# Bpod_RasPi_Shim_r1.net
KiCad netlist of a schematic drawn in EAGLE
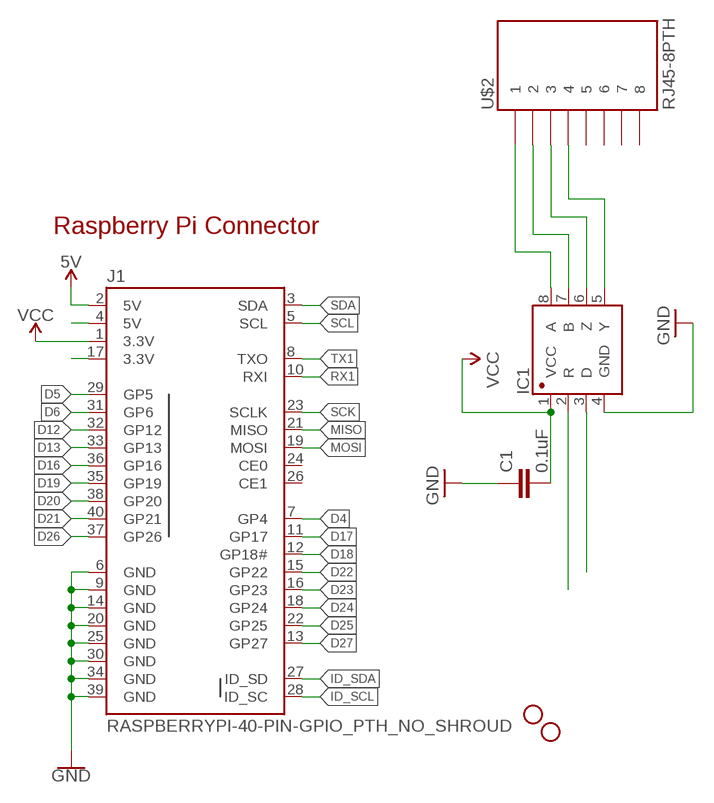
[diagram p0: schematic, sheet 1]

(export (version "E")
  (design (tool "Eeschema 10.0.6"))
  (components
    (comp (ref "C1")
      (value "0.1uF")
      (footprint "eagle-import:0805")
      (libsource (lib "eagle-import") (part "1.0UF-0805-25V-(+80/-20%)"))
    )
    (comp (ref "H3")
      (value "STAND-OFFTIGHT")
      (footprint "eagle-import:STAND-OFF-TIGHT")
      (libsource (lib "eagle-import") (part "STAND-OFFTIGHT"))
    )
    (comp (ref "H4")
      (value "STAND-OFFTIGHT")
      (footprint "eagle-import:STAND-OFF-TIGHT")
      (libsource (lib "eagle-import") (part "STAND-OFFTIGHT"))
    )
    (comp (ref "IC1")
      (value "SN65HVD31DR")
      (footprint "eagle-import:SO08")
      (libsource (lib "eagle-import") (part "SN65HVD31DR"))
    )
    (comp (ref "J1")
      (value "RASPBERRYPI-40-PIN-GPIO_PTH_NO_SHROUD")
      (footprint "eagle-import:2X20")
      (libsource (lib "eagle-import") (part "RASPBERRYPI-40-PIN-GPIO_PTH_NO_SHROUD"))
    )
    (comp (ref "U$2")
      (value "RJ45-8PTH")
      (footprint "eagle-import:RJ45-8")
      (libsource (lib "eagle-import") (part "RJ45-8PTH"))
    )
  )
  (nets
    (net (code "1") (name "5V") (class "Default")
      (node (ref "J1") (pin "2") (pinfunction "5V_2") (pintype "power_in"))
    )
    (net (code "2") (name "D4") (class "Default")
      (node (ref "J1") (pin "7") (pinfunction "GP4_7") (pintype "bidirectional"))
    )
    (net (code "3") (name "D5") (class "Default")
      (node (ref "J1") (pin "29") (pinfunction "GP5_29") (pintype "bidirectional"))
    )
    (net (code "4") (name "D6") (class "Default")
      (node (ref "J1") (pin "31") (pinfunction "GP6_31") (pintype "bidirectional"))
    )
    (net (code "5") (name "D12") (class "Default")
      (node (ref "J1") (pin "32") (pinfunction "GP12_32") (pintype "bidirectional"))
    )
    (net (code "6") (name "D13") (class "Default")
      (node (ref "J1") (pin "33") (pinfunction "GP13_33") (pintype "bidirectional"))
    )
    (net (code "7") (name "D16") (class "Default")
      (node (ref "J1") (pin "36") (pinfunction "GP16_36") (pintype "bidirectional"))
    )
    (net (code "8") (name "D17") (class "Default")
      (node (ref "J1") (pin "11") (pinfunction "GP17_11") (pintype "bidirectional"))
    )
    (net (code "9") (name "D18") (class "Default")
      (node (ref "J1") (pin "12") (pinfunction "GP18#_12") (pintype "bidirectional"))
    )
    (net (code "10") (name "D19") (class "Default")
      (node (ref "J1") (pin "35") (pinfunction "GP19_35") (pintype "bidirectional"))
    )
    (net (code "11") (name "D20") (class "Default")
      (node (ref "J1") (pin "38") (pinfunction "GP20_38") (pintype "bidirectional"))
    )
    (net (code "12") (name "D21") (class "Default")
      (node (ref "J1") (pin "40") (pinfunction "GP21_40") (pintype "bidirectional"))
    )
    (net (code "13") (name "D22") (class "Default")
      (node (ref "J1") (pin "15") (pinfunction "GP22_15") (pintype "bidirectional"))
    )
    (net (code "14") (name "D23") (class "Default")
      (node (ref "J1") (pin "16") (pinfunction "GP23_16") (pintype "bidirectional"))
    )
    (net (code "15") (name "D24") (class "Default")
      (node (ref "J1") (pin "18") (pinfunction "GP24_18") (pintype "bidirectional"))
    )
    (net (code "16") (name "D25") (class "Default")
      (node (ref "J1") (pin "22") (pinfunction "GP25_22") (pintype "bidirectional"))
    )
    (net (code "17") (name "D26") (class "Default")
      (node (ref "J1") (pin "37") (pinfunction "GP26_37") (pintype "bidirectional"))
    )
    (net (code "18") (name "D27") (class "Default")
      (node (ref "J1") (pin "13") (pinfunction "GP27_13") (pintype "bidirectional"))
    )
    (net (code "19") (name "GND") (class "Default")
      (node (ref "C1") (pin "1") (pinfunction "1_1") (pintype "passive"))
      (node (ref "IC1") (pin "4") (pinfunction "GND_4") (pintype "bidirectional"))
      (node (ref "J1") (pin "14") (pinfunction "GND_14") (pintype "power_in"))
      (node (ref "J1") (pin "20") (pinfunction "GND_20") (pintype "power_in"))
      (node (ref "J1") (pin "25") (pinfunction "GND_25") (pintype "power_in"))
      (node (ref "J1") (pin "30") (pinfunction "GND_30") (pintype "power_in"))
      (node (ref "J1") (pin "34") (pinfunction "GND_34") (pintype "power_in"))
      (node (ref "J1") (pin "39") (pinfunction "GND_39") (pintype "power_in"))
      (node (ref "J1") (pin "6") (pinfunction "GND_6") (pintype "power_in"))
      (node (ref "J1") (pin "9") (pinfunction "GND_9") (pintype "power_in"))
    )
    (net (code "20") (name "ID_SCL") (class "Default")
      (node (ref "J1") (pin "28") (pinfunction "ID_SC_28") (pintype "bidirectional"))
    )
    (net (code "21") (name "ID_SDA") (class "Default")
      (node (ref "J1") (pin "27") (pinfunction "ID_SD_27") (pintype "bidirectional"))
    )
    (net (code "22") (name "MISO") (class "Default")
      (node (ref "J1") (pin "21") (pinfunction "MISO_21") (pintype "input"))
    )
    (net (code "23") (name "MOSI") (class "Default")
      (node (ref "J1") (pin "19") (pinfunction "MOSI_19") (pintype "output"))
    )
    (net (code "24") (name "Net-(IC1-A)") (class "Default")
      (node (ref "IC1") (pin "8") (pinfunction "A_8") (pintype "bidirectional"))
      (node (ref "U$2") (pin "1") (pinfunction "1_1") (pintype "bidirectional"))
    )
    (net (code "25") (name "Net-(IC1-B)") (class "Default")
      (node (ref "IC1") (pin "7") (pinfunction "B_7") (pintype "bidirectional"))
      (node (ref "U$2") (pin "2") (pinfunction "2_2") (pintype "bidirectional"))
    )
    (net (code "26") (name "Net-(IC1-Y)") (class "Default")
      (node (ref "IC1") (pin "5") (pinfunction "Y_5") (pintype "bidirectional"))
      (node (ref "U$2") (pin "4") (pinfunction "4_4") (pintype "bidirectional"))
    )
    (net (code "27") (name "Net-(IC1-Z)") (class "Default")
      (node (ref "IC1") (pin "6") (pinfunction "Z_6") (pintype "bidirectional"))
      (node (ref "U$2") (pin "3") (pinfunction "3_3") (pintype "bidirectional"))
    )
    (net (code "28") (name "RX1") (class "Default")
      (node (ref "IC1") (pin "2") (pinfunction "R_2") (pintype "bidirectional"))
      (node (ref "J1") (pin "10") (pinfunction "RXI_10") (pintype "input"))
    )
    (net (code "29") (name "SCK") (class "Default")
      (node (ref "J1") (pin "23") (pinfunction "SCLK_23") (pintype "output"))
    )
    (net (code "30") (name "SCL") (class "Default")
      (node (ref "J1") (pin "5") (pinfunction "SCL_5") (pintype "bidirectional"))
    )
    (net (code "31") (name "SDA") (class "Default")
      (node (ref "J1") (pin "3") (pinfunction "SDA_3") (pintype "bidirectional"))
    )
    (net (code "32") (name "TX1") (class "Default")
      (node (ref "IC1") (pin "3") (pinfunction "D_3") (pintype "bidirectional"))
      (node (ref "J1") (pin "8") (pinfunction "TXO_8") (pintype "output"))
    )
    (net (code "33") (name "VCC") (class "Default")
      (node (ref "C1") (pin "2") (pinfunction "2_2") (pintype "passive"))
      (node (ref "IC1") (pin "1") (pinfunction "VCC_1") (pintype "bidirectional"))
      (node (ref "J1") (pin "1") (pinfunction "3.3V_1") (pintype "power_in"))
    )
    (net (code "34") (name "unconnected-(J1-3.3V-Pad17)") (class "Default")
      (node (ref "J1") (pin "17") (pinfunction "3.3V_17") (pintype "power_in"))
    )
    (net (code "35") (name "unconnected-(J1-5V-Pad4)") (class "Default")
      (node (ref "J1") (pin "4") (pinfunction "5V_4") (pintype "power_in"))
    )
    (net (code "36") (name "unconnected-(J1-CE0-Pad24)") (class "Default")
      (node (ref "J1") (pin "24") (pinfunction "CE0_24") (pintype "output"))
    )
    (net (code "37") (name "unconnected-(J1-CE1-Pad26)") (class "Default")
      (node (ref "J1") (pin "26") (pinfunction "CE1_26") (pintype "output"))
    )
    (net (code "38") (name "unconnected-(U$2-Pad5)") (class "Default")
      (node (ref "U$2") (pin "5") (pinfunction "5_5") (pintype "bidirectional"))
    )
    (net (code "39") (name "unconnected-(U$2-Pad6)") (class "Default")
      (node (ref "U$2") (pin "6") (pinfunction "6_6") (pintype "bidirectional"))
    )
    (net (code "40") (name "unconnected-(U$2-Pad7)") (class "Default")
      (node (ref "U$2") (pin "7") (pinfunction "7_7") (pintype "bidirectional"))
    )
    (net (code "41") (name "unconnected-(U$2-Pad8)") (class "Default")
      (node (ref "U$2") (pin "8") (pinfunction "8_8") (pintype "bidirectional"))
    )
  )
)
